# Slip_Ring_In-Line_Breakout_Board.net
KiCad netlist of a schematic drawn in EAGLE
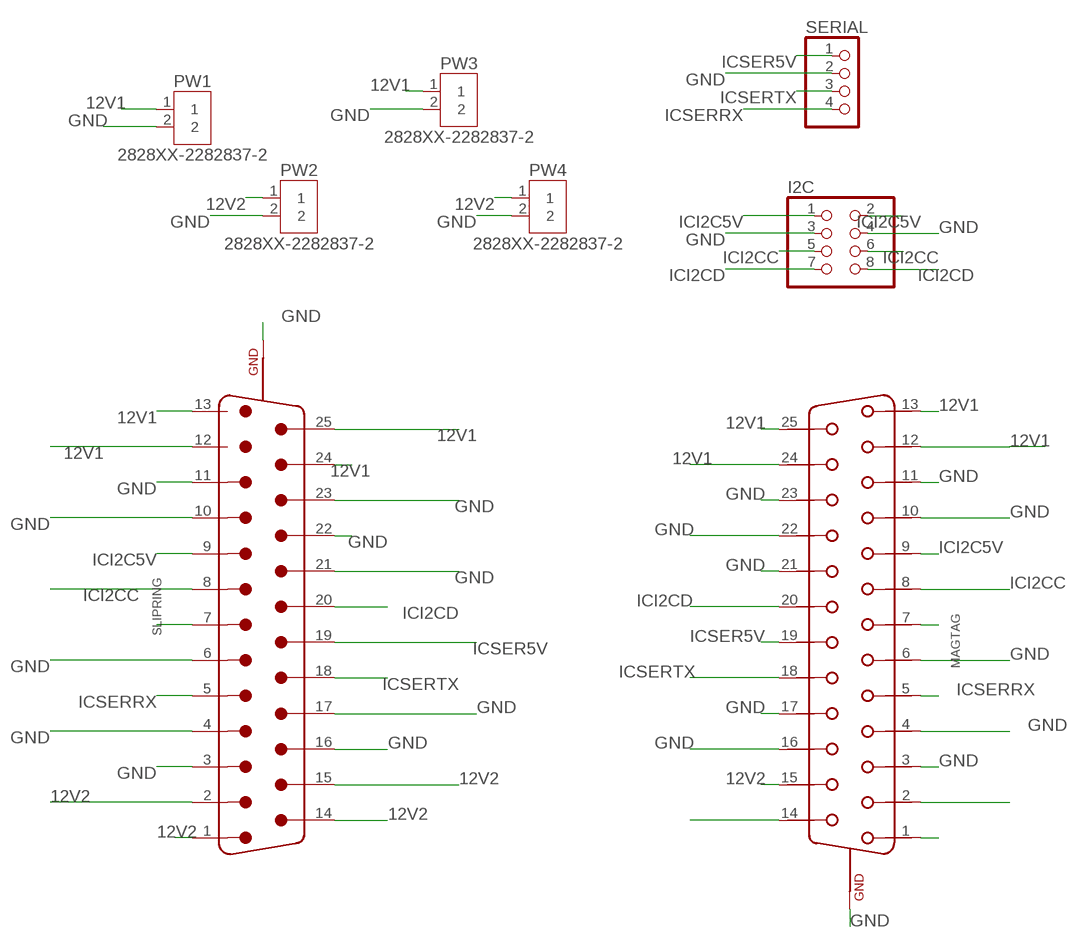
[diagram p0: schematic, sheet 1]

(export (version "E")
  (design (tool "Eeschema 10.0.6"))
  (components
    (comp (ref "I2C")
      (value "PINHD-2X4")
      (footprint "eagle-import:2X04")
      (fields (field (name "MF") "MULTICOMP PRO") (field (name "MPN") "2213S-08G"))
      (libsource (lib "eagle-import") (part "PINHD-2X4"))
    )
    (comp (ref "MAGTAG")
      (value "WE-D-SUB_THT_UNC4/40_214611023")
      (footprint "eagle-import:WE-D-SUB_THT_UNC4_40_214611023")
      (fields (field (name "MF") "WURTH ELEKTRONIK") (field (name "MPN") "61802525123"))
      (libsource (lib "eagle-import") (part "WE-D-SUB_THT_UNC4/40_214611023"))
    )
    (comp (ref "PW1")
      (value "2828XX-2282837-2")
      (footprint "eagle-import:TERMBLK_508-2N")
      (fields
        (field (name "MANUFACTURER") "TE Connectivity")
        (field (name "MPN") "282837-2")
        (field (name "MF") "AMPHENOL ANYTEK")
        (field (name "MPN_1") "20020316-H021B01LF")
      )
      (libsource (lib "eagle-import") (part "2828XX-2282837-2"))
    )
    (comp (ref "PW2")
      (value "2828XX-2282837-2")
      (footprint "eagle-import:TERMBLK_508-2N")
      (fields
        (field (name "MANUFACTURER") "TE Connectivity")
        (field (name "MPN") "282837-2")
        (field (name "MF") "AMPHENOL ANYTEK")
        (field (name "MPN_1") "20020316-H021B01LF")
      )
      (libsource (lib "eagle-import") (part "2828XX-2282837-2"))
    )
    (comp (ref "PW3")
      (value "2828XX-2282837-2")
      (footprint "eagle-import:TERMBLK_508-2N")
      (fields
        (field (name "MANUFACTURER") "TE Connectivity")
        (field (name "MPN") "282837-2")
        (field (name "MF") "AMPHENOL ANYTEK")
        (field (name "MPN_1") "20020316-H021B01LF")
      )
      (libsource (lib "eagle-import") (part "2828XX-2282837-2"))
    )
    (comp (ref "PW4")
      (value "2828XX-2282837-2")
      (footprint "eagle-import:TERMBLK_508-2N")
      (fields
        (field (name "MANUFACTURER") "TE Connectivity")
        (field (name "MPN") "282837-2")
        (field (name "MF") "AMPHENOL ANYTEK")
        (field (name "MPN_1") "20020316-H021B01LF")
      )
      (libsource (lib "eagle-import") (part "2828XX-2282837-2"))
    )
    (comp (ref "SERIAL")
      (value "PINHD-1X4")
      (footprint "eagle-import:1X04")
      (fields (field (name "MF") "MOLEX") (field (name "MPN") "22-28-4041"))
      (libsource (lib "eagle-import") (part "PINHD-1X4"))
    )
    (comp (ref "SLIPRING")
      (value "WE-D-SUB_THT_UNC4/40_214111023")
      (footprint "eagle-import:WE-D-SUB_THT_UNC4_40_214111023")
      (fields (field (name "MF") "WURTH ELEKTRONIK") (field (name "MPN") "61802525023"))
      (libsource (lib "eagle-import") (part "WE-D-SUB_THT_UNC4/40_214111023"))
    )
  )
  (nets
    (net (code "1") (name "/12V1") (class "Default")
      (node (ref "MAGTAG") (pin "12") (pinfunction "2_12") (pintype "passive"))
      (node (ref "MAGTAG") (pin "13") (pinfunction "1_13") (pintype "passive"))
      (node (ref "MAGTAG") (pin "24") (pinfunction "15_24") (pintype "passive"))
      (node (ref "MAGTAG") (pin "25") (pinfunction "14_25") (pintype "passive"))
      (node (ref "PW1") (pin "1") (pinfunction "1_1") (pintype "bidirectional"))
      (node (ref "PW3") (pin "1") (pinfunction "1_1") (pintype "bidirectional"))
      (node (ref "SLIPRING") (pin "12") (pinfunction "12_12") (pintype "passive"))
      (node (ref "SLIPRING") (pin "13") (pinfunction "13_13") (pintype "passive"))
      (node (ref "SLIPRING") (pin "24") (pinfunction "24_24") (pintype "passive"))
      (node (ref "SLIPRING") (pin "25") (pinfunction "25_25") (pintype "passive"))
    )
    (net (code "2") (name "/12V2") (class "Default")
      (node (ref "MAGTAG") (pin "14") (pinfunction "25_14") (pintype "passive"))
      (node (ref "MAGTAG") (pin "15") (pinfunction "24_15") (pintype "passive"))
      (node (ref "PW2") (pin "1") (pinfunction "1_1") (pintype "bidirectional"))
      (node (ref "PW4") (pin "1") (pinfunction "1_1") (pintype "bidirectional"))
      (node (ref "SLIPRING") (pin "1") (pinfunction "1_1") (pintype "passive"))
      (node (ref "SLIPRING") (pin "14") (pinfunction "14_14") (pintype "passive"))
      (node (ref "SLIPRING") (pin "15") (pinfunction "15_15") (pintype "passive"))
      (node (ref "SLIPRING") (pin "2") (pinfunction "2_2") (pintype "passive"))
    )
    (net (code "3") (name "/GND") (class "Default")
      (node (ref "I2C") (pin "3") (pinfunction "3_3") (pintype "passive"))
      (node (ref "I2C") (pin "4") (pinfunction "4_4") (pintype "passive"))
      (node (ref "MAGTAG") (pin "10") (pinfunction "4_10") (pintype "passive"))
      (node (ref "MAGTAG") (pin "11") (pinfunction "3_11") (pintype "passive"))
      (node (ref "MAGTAG") (pin "16") (pinfunction "23_16") (pintype "passive"))
      (node (ref "MAGTAG") (pin "17") (pinfunction "22_17") (pintype "passive"))
      (node (ref "MAGTAG") (pin "21") (pinfunction "18_21") (pintype "passive"))
      (node (ref "MAGTAG") (pin "22") (pinfunction "17_22") (pintype "passive"))
      (node (ref "MAGTAG") (pin "23") (pinfunction "16_23") (pintype "passive"))
      (node (ref "MAGTAG") (pin "3") (pinfunction "11_3") (pintype "passive"))
      (node (ref "MAGTAG") (pin "4") (pinfunction "10_4") (pintype "passive"))
      (node (ref "MAGTAG") (pin "6") (pinfunction "8_6") (pintype "passive"))
      (node (ref "MAGTAG") (pin "Z1") (pinfunction "GND_Z1") (pintype "power_in"))
      (node (ref "MAGTAG") (pin "Z2") (pinfunction "GND_Z2") (pintype "power_in"))
      (node (ref "PW1") (pin "2") (pinfunction "2_2") (pintype "bidirectional"))
      (node (ref "PW2") (pin "2") (pinfunction "2_2") (pintype "bidirectional"))
      (node (ref "PW3") (pin "2") (pinfunction "2_2") (pintype "bidirectional"))
      (node (ref "PW4") (pin "2") (pinfunction "2_2") (pintype "bidirectional"))
      (node (ref "SERIAL") (pin "2") (pinfunction "2_2") (pintype "passive"))
      (node (ref "SLIPRING") (pin "10") (pinfunction "10_10") (pintype "passive"))
      (node (ref "SLIPRING") (pin "11") (pinfunction "11_11") (pintype "passive"))
      (node (ref "SLIPRING") (pin "16") (pinfunction "16_16") (pintype "passive"))
      (node (ref "SLIPRING") (pin "17") (pinfunction "17_17") (pintype "passive"))
      (node (ref "SLIPRING") (pin "21") (pinfunction "21_21") (pintype "passive"))
      (node (ref "SLIPRING") (pin "22") (pinfunction "22_22") (pintype "passive"))
      (node (ref "SLIPRING") (pin "23") (pinfunction "23_23") (pintype "passive"))
      (node (ref "SLIPRING") (pin "3") (pinfunction "3_3") (pintype "passive"))
      (node (ref "SLIPRING") (pin "4") (pinfunction "4_4") (pintype "passive"))
      (node (ref "SLIPRING") (pin "6") (pinfunction "6_6") (pintype "passive"))
      (node (ref "SLIPRING") (pin "Z1") (pinfunction "GND_Z1") (pintype "power_in"))
      (node (ref "SLIPRING") (pin "Z2") (pinfunction "GND_Z2") (pintype "power_in"))
    )
    (net (code "4") (name "/ICI2C5V") (class "Default")
      (node (ref "I2C") (pin "1") (pinfunction "1_1") (pintype "passive"))
      (node (ref "I2C") (pin "2") (pinfunction "2_2") (pintype "passive"))
      (node (ref "MAGTAG") (pin "9") (pinfunction "5_9") (pintype "passive"))
      (node (ref "SLIPRING") (pin "9") (pinfunction "9_9") (pintype "passive"))
    )
    (net (code "5") (name "/ICI2CC") (class "Default")
      (node (ref "I2C") (pin "5") (pinfunction "5_5") (pintype "passive"))
      (node (ref "I2C") (pin "6") (pinfunction "6_6") (pintype "passive"))
      (node (ref "MAGTAG") (pin "8") (pinfunction "6_8") (pintype "passive"))
      (node (ref "SLIPRING") (pin "8") (pinfunction "8_8") (pintype "passive"))
    )
    (net (code "6") (name "/ICI2CD") (class "Default")
      (node (ref "I2C") (pin "7") (pinfunction "7_7") (pintype "passive"))
      (node (ref "I2C") (pin "8") (pinfunction "8_8") (pintype "passive"))
      (node (ref "MAGTAG") (pin "20") (pinfunction "19_20") (pintype "passive"))
      (node (ref "SLIPRING") (pin "20") (pinfunction "20_20") (pintype "passive"))
    )
    (net (code "7") (name "/ICSER5V") (class "Default")
      (node (ref "MAGTAG") (pin "19") (pinfunction "20_19") (pintype "passive"))
      (node (ref "SERIAL") (pin "1") (pinfunction "1_1") (pintype "passive"))
      (node (ref "SLIPRING") (pin "19") (pinfunction "19_19") (pintype "passive"))
    )
    (net (code "8") (name "/ICSERRX") (class "Default")
      (node (ref "MAGTAG") (pin "5") (pinfunction "9_5") (pintype "passive"))
      (node (ref "SERIAL") (pin "4") (pinfunction "4_4") (pintype "passive"))
      (node (ref "SLIPRING") (pin "5") (pinfunction "5_5") (pintype "passive"))
    )
    (net (code "9") (name "/ICSERTX") (class "Default")
      (node (ref "MAGTAG") (pin "18") (pinfunction "21_18") (pintype "passive"))
      (node (ref "SERIAL") (pin "3") (pinfunction "3_3") (pintype "passive"))
      (node (ref "SLIPRING") (pin "18") (pinfunction "18_18") (pintype "passive"))
    )
    (net (code "10") (name "unconnected-(MAGTAG-12-Pad2)") (class "Default")
      (node (ref "MAGTAG") (pin "2") (pinfunction "12_2") (pintype "passive"))
    )
    (net (code "11") (name "unconnected-(MAGTAG-13-Pad1)") (class "Default")
      (node (ref "MAGTAG") (pin "1") (pinfunction "13_1") (pintype "passive"))
    )
    (net (code "12") (name "unconnected-(MAGTAG-Pad7)") (class "Default")
      (node (ref "MAGTAG") (pin "7") (pinfunction "7_7") (pintype "passive"))
    )
    (net (code "13") (name "unconnected-(SLIPRING-Pad7)") (class "Default")
      (node (ref "SLIPRING") (pin "7") (pinfunction "7_7") (pintype "passive"))
    )
  )
)
